# PCB_design.net
KiCad netlist of a schematic drawn in EasyEDA
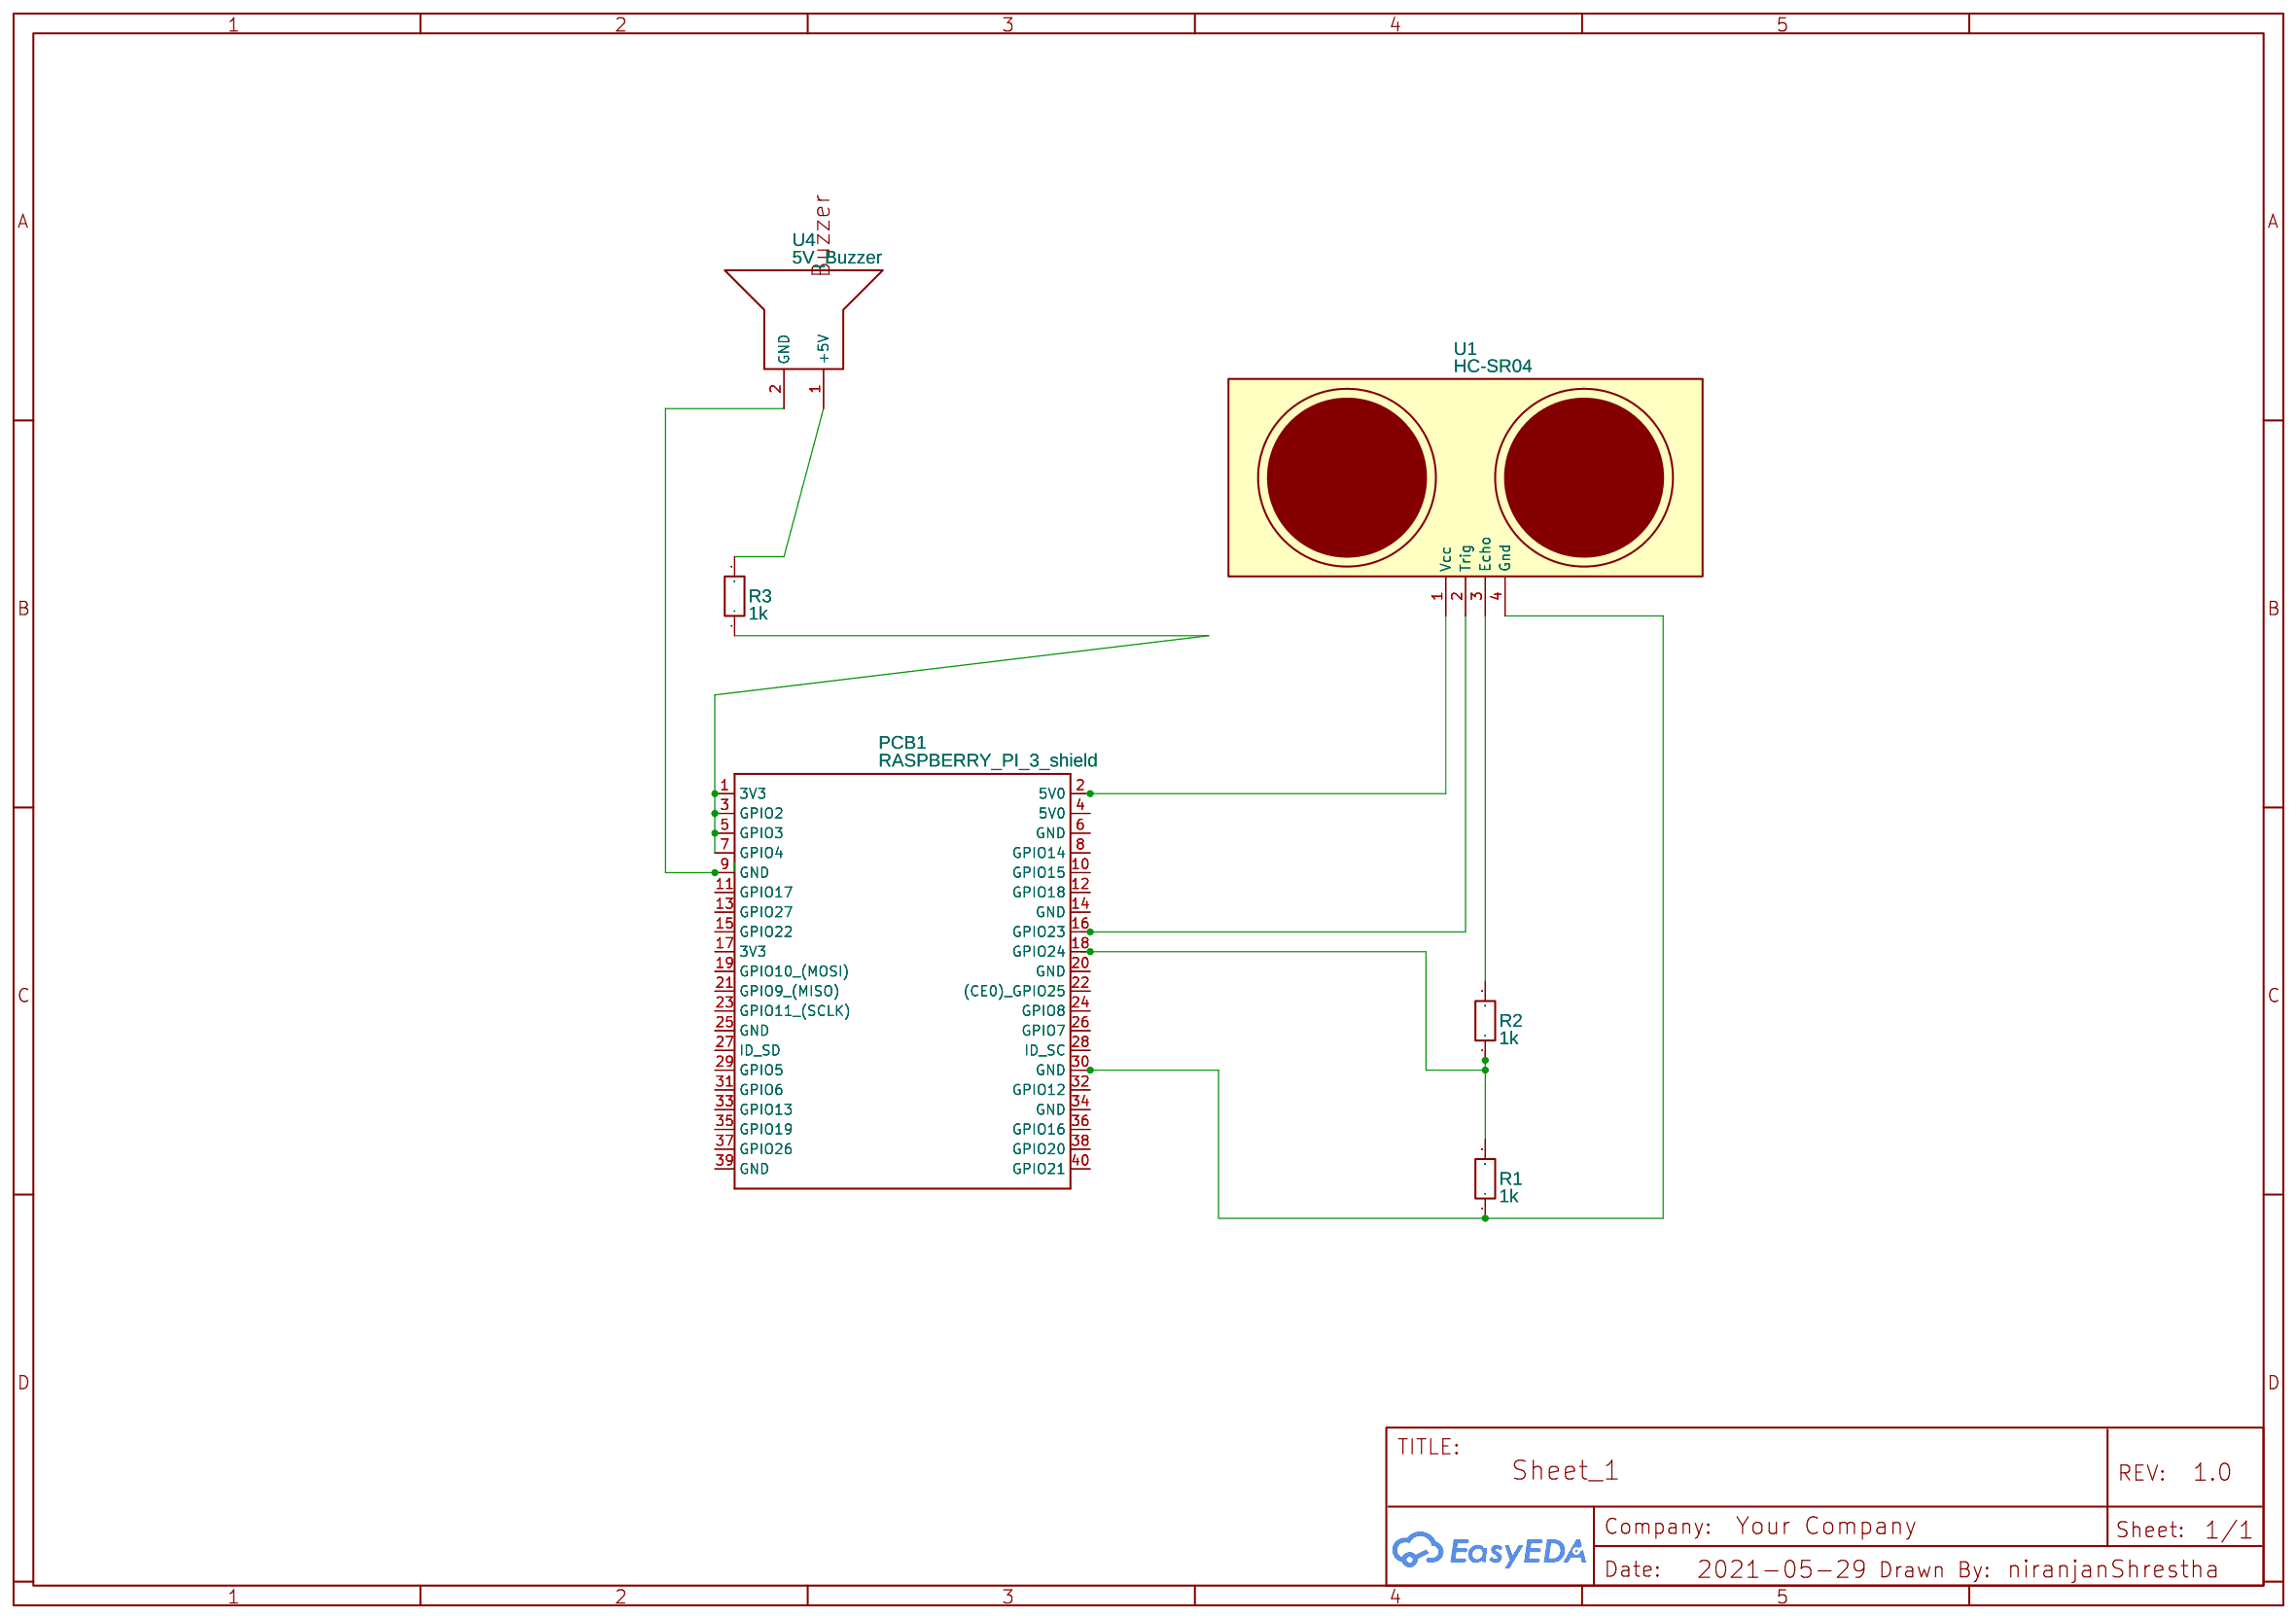
[diagram p0: schematic sheet]

(export (version "E")
  (design (tool "Eeschema 10.0.6"))
  (components
    (comp (ref "PCB1") (value "RASPBERRY_PI_3_shield") (libsource (lib "") (part "RASPBERRY_PI_3_shield")))
    (comp (ref "R1") (value "1k") (libsource (lib "") (part "R_0201_EU")))
    (comp (ref "R2") (value "1k") (libsource (lib "") (part "R_0201_EU")))
    (comp (ref "R3") (value "1k") (libsource (lib "") (part "R_0201_EU")))
    (comp (ref "U1") (value "HC-SR04") (libsource (lib "") (part "HC-SR04")))
    (comp (ref "U4")
      (value "5V_Buzzer")
      (fields (field (name "BOM_Manufacturer Part") "HN9650B"))
      (libsource (lib "") (part "5V_Buzzer"))
    )
  )
  (nets
    (net (code "1") (name "Net-(PCB1-GPIO2)") (class "Default")
      (node (ref "PCB1") (pin "1") (pinfunction "3V3_1") (pintype "unspecified"))
      (node (ref "PCB1") (pin "3") (pinfunction "GPIO2_3") (pintype "unspecified"))
      (node (ref "PCB1") (pin "5") (pinfunction "GPIO3_5") (pintype "unspecified"))
      (node (ref "PCB1") (pin "7") (pinfunction "GPIO4_7") (pintype "unspecified"))
      (node (ref "R3") (pin "1") (pinfunction "1_1") (pintype "unspecified"))
    )
    (net (code "2") (name "Net-(PCB1-GPIO23)") (class "Default")
      (node (ref "PCB1") (pin "16") (pinfunction "GPIO23_16") (pintype "unspecified"))
      (node (ref "U1") (pin "2") (pinfunction "Trig_2") (pintype "unspecified"))
    )
    (net (code "3") (name "Net-(PCB1-GPIO24)") (class "Default")
      (node (ref "PCB1") (pin "18") (pinfunction "GPIO24_18") (pintype "unspecified"))
      (node (ref "R1") (pin "2") (pinfunction "2_2") (pintype "unspecified"))
      (node (ref "R2") (pin "1") (pinfunction "1_1") (pintype "unspecified"))
    )
    (net (code "4") (name "Net-(U1-Echo)") (class "Default")
      (node (ref "R2") (pin "2") (pinfunction "2_2") (pintype "unspecified"))
      (node (ref "U1") (pin "3") (pinfunction "Echo_3") (pintype "unspecified"))
    )
    (net (code "5") (name "Net-(U1-Gnd)") (class "Default")
      (node (ref "PCB1") (pin "30") (pinfunction "GND_30") (pintype "unspecified"))
      (node (ref "R1") (pin "1") (pinfunction "1_1") (pintype "unspecified"))
      (node (ref "U1") (pin "4") (pinfunction "Gnd_4") (pintype "unspecified"))
    )
    (net (code "6") (name "Net-(U1-Vcc)") (class "Default")
      (node (ref "PCB1") (pin "2") (pinfunction "5V0_2") (pintype "unspecified"))
      (node (ref "U1") (pin "1") (pinfunction "Vcc_1") (pintype "unspecified"))
    )
    (net (code "7") (name "Net-(U4-+5V)") (class "Default")
      (node (ref "R3") (pin "2") (pinfunction "2_2") (pintype "unspecified"))
      (node (ref "U4") (pin "1") (pinfunction "+5V_1") (pintype "unspecified"))
    )
    (net (code "8") (name "Net-(U4-GND)") (class "Default")
      (node (ref "PCB1") (pin "9") (pinfunction "GND_9") (pintype "unspecified"))
      (node (ref "U4") (pin "2") (pinfunction "GND_2") (pintype "unspecified"))
    )
    (net (code "9") (name "unconnected-(PCB1-(CE0)_GPIO25-Pad22)") (class "Default")
      (node (ref "PCB1") (pin "22") (pinfunction "(CE0)_GPIO25_22") (pintype "unspecified"))
    )
    (net (code "10") (name "unconnected-(PCB1-3V3-Pad17)") (class "Default")
      (node (ref "PCB1") (pin "17") (pinfunction "3V3_17") (pintype "unspecified"))
    )
    (net (code "11") (name "unconnected-(PCB1-5V0-Pad4)") (class "Default")
      (node (ref "PCB1") (pin "4") (pinfunction "5V0_4") (pintype "unspecified"))
    )
    (net (code "12") (name "unconnected-(PCB1-GND-Pad6)") (class "Default")
      (node (ref "PCB1") (pin "6") (pinfunction "GND_6") (pintype "unspecified"))
    )
    (net (code "13") (name "unconnected-(PCB1-GND-Pad14)") (class "Default")
      (node (ref "PCB1") (pin "14") (pinfunction "GND_14") (pintype "unspecified"))
    )
    (net (code "14") (name "unconnected-(PCB1-GND-Pad20)") (class "Default")
      (node (ref "PCB1") (pin "20") (pinfunction "GND_20") (pintype "unspecified"))
    )
    (net (code "15") (name "unconnected-(PCB1-GND-Pad25)") (class "Default")
      (node (ref "PCB1") (pin "25") (pinfunction "GND_25") (pintype "unspecified"))
    )
    (net (code "16") (name "unconnected-(PCB1-GND-Pad34)") (class "Default")
      (node (ref "PCB1") (pin "34") (pinfunction "GND_34") (pintype "unspecified"))
    )
    (net (code "17") (name "unconnected-(PCB1-GND-Pad39)") (class "Default")
      (node (ref "PCB1") (pin "39") (pinfunction "GND_39") (pintype "unspecified"))
    )
    (net (code "18") (name "unconnected-(PCB1-GPIO5-Pad29)") (class "Default")
      (node (ref "PCB1") (pin "29") (pinfunction "GPIO5_29") (pintype "unspecified"))
    )
    (net (code "19") (name "unconnected-(PCB1-GPIO6-Pad31)") (class "Default")
      (node (ref "PCB1") (pin "31") (pinfunction "GPIO6_31") (pintype "unspecified"))
    )
    (net (code "20") (name "unconnected-(PCB1-GPIO7-Pad26)") (class "Default")
      (node (ref "PCB1") (pin "26") (pinfunction "GPIO7_26") (pintype "unspecified"))
    )
    (net (code "21") (name "unconnected-(PCB1-GPIO8-Pad24)") (class "Default")
      (node (ref "PCB1") (pin "24") (pinfunction "GPIO8_24") (pintype "unspecified"))
    )
    (net (code "22") (name "unconnected-(PCB1-GPIO9_(MISO)-Pad21)") (class "Default")
      (node (ref "PCB1") (pin "21") (pinfunction "GPIO9_(MISO)_21") (pintype "unspecified"))
    )
    (net (code "23") (name "unconnected-(PCB1-GPIO10_(MOSI)-Pad19)") (class "Default")
      (node (ref "PCB1") (pin "19") (pinfunction "GPIO10_(MOSI)_19") (pintype "unspecified"))
    )
    (net (code "24") (name "unconnected-(PCB1-GPIO11_(SCLK)-Pad23)") (class "Default")
      (node (ref "PCB1") (pin "23") (pinfunction "GPIO11_(SCLK)_23") (pintype "unspecified"))
    )
    (net (code "25") (name "unconnected-(PCB1-GPIO12-Pad32)") (class "Default")
      (node (ref "PCB1") (pin "32") (pinfunction "GPIO12_32") (pintype "unspecified"))
    )
    (net (code "26") (name "unconnected-(PCB1-GPIO13-Pad33)") (class "Default")
      (node (ref "PCB1") (pin "33") (pinfunction "GPIO13_33") (pintype "unspecified"))
    )
    (net (code "27") (name "unconnected-(PCB1-GPIO14-Pad8)") (class "Default")
      (node (ref "PCB1") (pin "8") (pinfunction "GPIO14_8") (pintype "unspecified"))
    )
    (net (code "28") (name "unconnected-(PCB1-GPIO15-Pad10)") (class "Default")
      (node (ref "PCB1") (pin "10") (pinfunction "GPIO15_10") (pintype "unspecified"))
    )
    (net (code "29") (name "unconnected-(PCB1-GPIO16-Pad36)") (class "Default")
      (node (ref "PCB1") (pin "36") (pinfunction "GPIO16_36") (pintype "unspecified"))
    )
    (net (code "30") (name "unconnected-(PCB1-GPIO17-Pad11)") (class "Default")
      (node (ref "PCB1") (pin "11") (pinfunction "GPIO17_11") (pintype "unspecified"))
    )
    (net (code "31") (name "unconnected-(PCB1-GPIO18-Pad12)") (class "Default")
      (node (ref "PCB1") (pin "12") (pinfunction "GPIO18_12") (pintype "unspecified"))
    )
    (net (code "32") (name "unconnected-(PCB1-GPIO19-Pad35)") (class "Default")
      (node (ref "PCB1") (pin "35") (pinfunction "GPIO19_35") (pintype "unspecified"))
    )
    (net (code "33") (name "unconnected-(PCB1-GPIO20-Pad38)") (class "Default")
      (node (ref "PCB1") (pin "38") (pinfunction "GPIO20_38") (pintype "unspecified"))
    )
    (net (code "34") (name "unconnected-(PCB1-GPIO21-Pad40)") (class "Default")
      (node (ref "PCB1") (pin "40") (pinfunction "GPIO21_40") (pintype "unspecified"))
    )
    (net (code "35") (name "unconnected-(PCB1-GPIO22-Pad15)") (class "Default")
      (node (ref "PCB1") (pin "15") (pinfunction "GPIO22_15") (pintype "unspecified"))
    )
    (net (code "36") (name "unconnected-(PCB1-GPIO26-Pad37)") (class "Default")
      (node (ref "PCB1") (pin "37") (pinfunction "GPIO26_37") (pintype "unspecified"))
    )
    (net (code "37") (name "unconnected-(PCB1-GPIO27-Pad13)") (class "Default")
      (node (ref "PCB1") (pin "13") (pinfunction "GPIO27_13") (pintype "unspecified"))
    )
    (net (code "38") (name "unconnected-(PCB1-ID_SC-Pad28)") (class "Default")
      (node (ref "PCB1") (pin "28") (pinfunction "ID_SC_28") (pintype "unspecified"))
    )
    (net (code "39") (name "unconnected-(PCB1-ID_SD-Pad27)") (class "Default")
      (node (ref "PCB1") (pin "27") (pinfunction "ID_SD_27") (pintype "unspecified"))
    )
  )
)
